# TEMPLATE_Connectors.net
KiCad netlist of a schematic drawn in Altium Designer
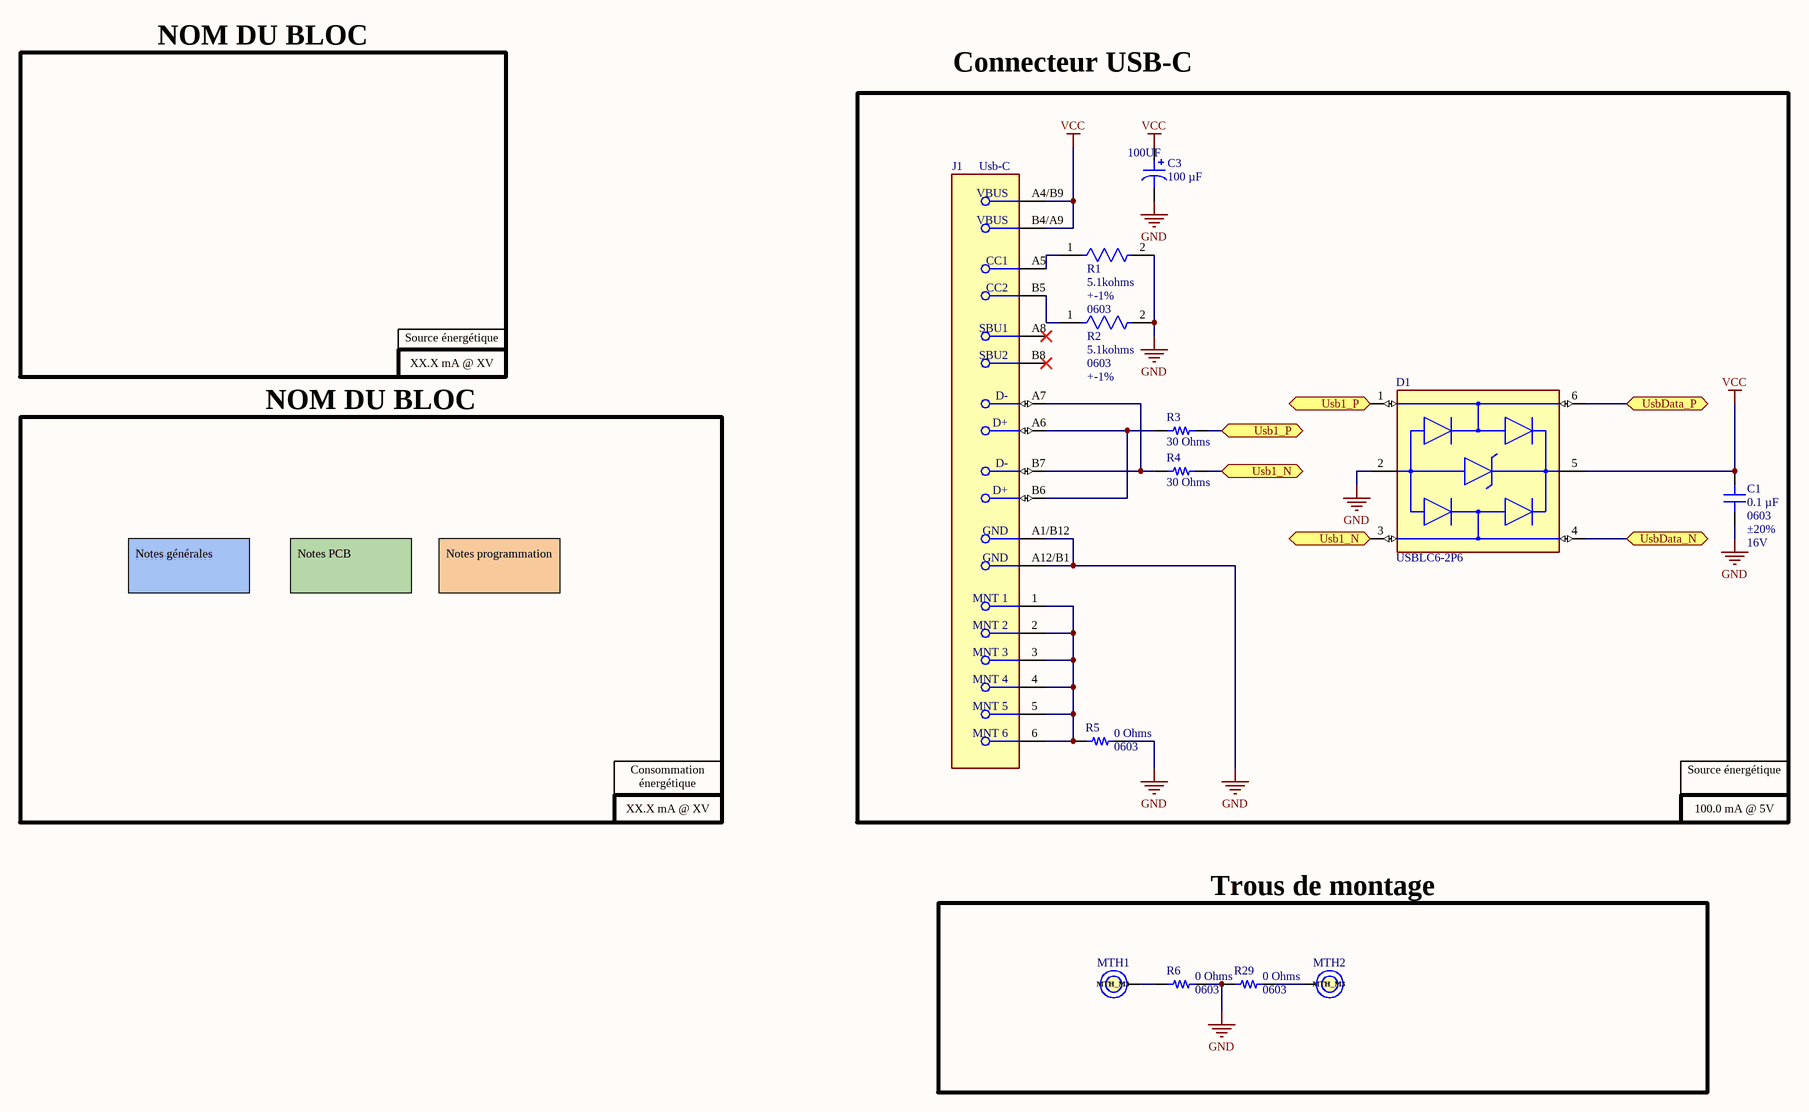
[diagram p0: TEMPLATE_Connectors.SchDoc]

(export (version "E")
  (design (tool "Eeschema 10.0.6"))
  (components
    (comp (ref "C1")
      (value "0.1 µF")
      (footprint "CAP 0603_1608")
      (description "CAP CER 0.1UF 16V X7R 0603")
      (fields
        (field (name "PART NUMBER") "KGM15AR71C104MM")
        (field (name "MANUFACTURER") "KYOCERA AVX")
        (field (name "PACKAGE / CASE") "0603")
        (field (name "TOLERANCE") "±20%")
        (field (name "VOLTAGE - RATED") "16V")
      )
      (libsource (lib "Celestial Altium Library - altium_library") (part "Capacitor"))
    )
    (comp (ref "C3")
      (value "100 µF")
      (footprint "CAP ALSMD 5.3MM H5.4MM")
      (description "CAP ALUM 100UF 20% 10V SMD")
      (fields
        (field (name "PART NUMBER") "EEE-1AA101WR")
        (field (name "MANUFACTURER") "Panasonic Electronic Components")
      )
      (libsource (lib "Celestial Altium Library - altium_library") (part "Polarised Capacitor"))
    )
    (comp (ref "D1")
      (value "USBLC6-2P6")
      (footprint "FP-SOT-666-MFG")
      (description "TVS DIODE 5.25V 17V SOT666")
      (libsource (lib "Altium Content Vault") (part "c871e55f7e3243d341edbd671b98d92"))
    )
    (comp (ref "J1")
      (value "Usb-C")
      (footprint "FP-DX07S016JA1R1500-MFG")
      (description "CONN RCP USB2.0 TYP C 24P SMD RA")
      (libsource (lib "Altium Content Vault") (part "7f3e9989102a0f22bff9cb010881d34"))
    )
    (comp (ref "MTH1")
      (value "MTH_M3")
      (footprint "MTH_M3")
      (description "MTH - MOUNTING HOLE M3 PLATED - M3")
      (fields (field (name "SOURCE") "CEGEP_SHERBROOKE_TGE_LIBRARY.SchLib"))
      (libsource (lib "Cegep de Sherbrooke") (part "MTH_M7"))
    )
    (comp (ref "MTH2")
      (value "MTH_M3")
      (footprint "MTH_M3")
      (description "MTH - MOUNTING HOLE M3 PLATED - M3")
      (fields (field (name "SOURCE") "CEGEP_SHERBROOKE_TGE_LIBRARY.SchLib"))
      (libsource (lib "Cegep de Sherbrooke") (part "MTH_M7"))
    )
    (comp (ref "R1")
      (value "5.1kohms")
      (footprint "FP-AC0603-MFG")
      (description "RES 5.1KΩ 1.00% 0.1W 0603")
      (fields (field (name "TOLERANCE") "1%"))
      (libsource (lib "Altium Content Vault") (part "1029c3af85768c4190bb7ad29bc67b5"))
    )
    (comp (ref "R2")
      (value "5.1kohms")
      (footprint "FP-AC0603-MFG")
      (description "RES 5.1KΩ 1.00% 0.1W 0603")
      (fields (field (name "TOLERANCE") "1%"))
      (libsource (lib "Altium Content Vault") (part "1029c3af85768c4190bb7ad29bc67b5"))
    )
    (comp (ref "R3")
      (value "30 Ohms")
      (footprint "RES 0603_1608")
      (description "RES SMD 30 OHM 5% 1/4W 0603")
      (fields (field (name "PART NUMBER") "ESR03EZPJ300") (field (name "MANUFACTURER") "Rohm Semiconductor"))
      (libsource (lib "Celestial Altium Library - altium_library") (part "Resistor"))
    )
    (comp (ref "R4")
      (value "30 Ohms")
      (footprint "RES 0603_1608")
      (description "RES SMD 30 OHM 5% 1/4W 0603")
      (fields (field (name "PART NUMBER") "ESR03EZPJ300") (field (name "MANUFACTURER") "Rohm Semiconductor"))
      (libsource (lib "Celestial Altium Library - altium_library") (part "Resistor"))
    )
    (comp (ref "R5")
      (value "0 Ohms")
      (footprint "RES 0603_1608")
      (description "RESA-AS 0603 0R JUMPER 100MW")
      (fields
        (field (name "PART NUMBER") "CR0603AJ/-000EAS")
        (field (name "MANUFACTURER") "Bourns Inc.")
        (field (name "SUPPLIER DEVICE PACKAGE") "0603")
      )
      (libsource (lib "Celestial Altium Library - altium_library") (part "Resistor"))
    )
    (comp (ref "R6")
      (value "0 Ohms")
      (footprint "RES 0603_1608")
      (description "RESA-AS 0603 0R JUMPER 100MW")
      (fields
        (field (name "PART NUMBER") "CR0603AJ/-000EAS")
        (field (name "MANUFACTURER") "Bourns Inc.")
        (field (name "SUPPLIER DEVICE PACKAGE") "0603")
      )
      (libsource (lib "Celestial Altium Library - altium_library") (part "Resistor"))
    )
    (comp (ref "R29")
      (value "0 Ohms")
      (footprint "RES 0603_1608")
      (description "RESA-AS 0603 0R JUMPER 100MW")
      (fields
        (field (name "PART NUMBER") "CR0603AJ/-000EAS")
        (field (name "MANUFACTURER") "Bourns Inc.")
        (field (name "SUPPLIER DEVICE PACKAGE") "0603")
      )
      (libsource (lib "Celestial Altium Library - altium_library") (part "Resistor"))
    )
  )
  (nets
    (net (code "1") (name "/Usb1_N") (class "Default")
      (node (ref "D1") (pin "3") (pinfunction "I/O2_3") (pintype "bidirectional"))
      (node (ref "R4") (pin "2") (pinfunction "2_2") (pintype "passive"))
    )
    (net (code "2") (name "/Usb1_P") (class "Default")
      (node (ref "D1") (pin "1") (pinfunction "I/O1_1") (pintype "bidirectional"))
      (node (ref "R3") (pin "2") (pinfunction "2_2") (pintype "passive"))
    )
    (net (code "3") (name "/UsbData_N") (class "Default")
      (node (ref "D1") (pin "4") (pinfunction "I/O2_4") (pintype "bidirectional"))
    )
    (net (code "4") (name "/UsbData_P") (class "Default")
      (node (ref "D1") (pin "6") (pinfunction "I/O1_6") (pintype "bidirectional"))
    )
    (net (code "5") (name "GND") (class "Default")
      (node (ref "C1") (pin "1") (pinfunction "1_1") (pintype "passive"))
      (node (ref "C3") (pin "2") (pinfunction "2_2") (pintype "passive"))
      (node (ref "D1") (pin "2") (pinfunction "GND_2") (pintype "power_in"))
      (node (ref "J1") (pin "A1/B12") (pinfunction "GND_A1/B12") (pintype "power_in"))
      (node (ref "J1") (pin "A12/B1") (pinfunction "GND_A12/B1") (pintype "power_in"))
      (node (ref "R1") (pin "2") (pinfunction "2_2") (pintype "passive"))
      (node (ref "R2") (pin "2") (pinfunction "2_2") (pintype "passive"))
      (node (ref "R29") (pin "1") (pinfunction "1_1") (pintype "passive"))
      (node (ref "R5") (pin "2") (pinfunction "2_2") (pintype "passive"))
      (node (ref "R6") (pin "2") (pinfunction "2_2") (pintype "passive"))
    )
    (net (code "6") (name "Net-(J1-CC1)") (class "Default")
      (node (ref "J1") (pin "A5") (pinfunction "CC1_A5") (pintype "passive"))
      (node (ref "R1") (pin "1") (pinfunction "1_1") (pintype "passive"))
    )
    (net (code "7") (name "Net-(J1-CC2)") (class "Default")
      (node (ref "J1") (pin "B5") (pinfunction "CC2_B5") (pintype "passive"))
      (node (ref "R2") (pin "1") (pinfunction "1_1") (pintype "passive"))
    )
    (net (code "8") (name "Net-(J1-D+-PadA6)") (class "Default")
      (node (ref "J1") (pin "A6") (pinfunction "D+_A6") (pintype "bidirectional"))
      (node (ref "J1") (pin "B6") (pinfunction "D+_B6") (pintype "bidirectional"))
      (node (ref "R3") (pin "1") (pinfunction "1_1") (pintype "passive"))
    )
    (net (code "9") (name "Net-(J1-D--PadA7)") (class "Default")
      (node (ref "J1") (pin "A7") (pinfunction "D-_A7") (pintype "bidirectional"))
      (node (ref "J1") (pin "B7") (pinfunction "D-_B7") (pintype "bidirectional"))
      (node (ref "R4") (pin "1") (pinfunction "1_1") (pintype "passive"))
    )
    (net (code "10") (name "Net-(J1-MNT_1)") (class "Default")
      (node (ref "J1") (pin "1") (pinfunction "MNT_1_1") (pintype "passive"))
      (node (ref "J1") (pin "2") (pinfunction "MNT_2_2") (pintype "passive"))
      (node (ref "J1") (pin "3") (pinfunction "MNT_3_3") (pintype "passive"))
      (node (ref "J1") (pin "4") (pinfunction "MNT_4_4") (pintype "passive"))
      (node (ref "J1") (pin "5") (pinfunction "MNT_5_5") (pintype "passive"))
      (node (ref "J1") (pin "6") (pinfunction "MNT_6_6") (pintype "passive"))
      (node (ref "R5") (pin "1") (pinfunction "1_1") (pintype "passive"))
    )
    (net (code "11") (name "Net-(MTH1-Pad1)") (class "Default")
      (node (ref "MTH1") (pin "1") (pinfunction "1_1") (pintype "passive"))
      (node (ref "R6") (pin "1") (pinfunction "1_1") (pintype "passive"))
    )
    (net (code "12") (name "Net-(MTH2-Pad1)") (class "Default")
      (node (ref "MTH2") (pin "1") (pinfunction "1_1") (pintype "passive"))
      (node (ref "R29") (pin "2") (pinfunction "2_2") (pintype "passive"))
    )
    (net (code "13") (name "VCC") (class "Default")
      (node (ref "C1") (pin "2") (pinfunction "2_2") (pintype "passive"))
      (node (ref "C3") (pin "1") (pinfunction "1_1") (pintype "passive"))
      (node (ref "D1") (pin "5") (pinfunction "VBUS_5") (pintype "power_in"))
      (node (ref "J1") (pin "A4/B9") (pinfunction "VBUS_A4/B9") (pintype "power_in"))
      (node (ref "J1") (pin "B4/A9") (pinfunction "VBUS_B4/A9") (pintype "power_in"))
    )
    (net (code "14") (name "unconnected-(J1-SBU1-PadA8)") (class "Default")
      (node (ref "J1") (pin "A8") (pinfunction "SBU1_A8") (pintype "passive+no_connect"))
    )
    (net (code "15") (name "unconnected-(J1-SBU2-PadB8)") (class "Default")
      (node (ref "J1") (pin "B8") (pinfunction "SBU2_B8") (pintype "passive+no_connect"))
    )
  )
)
